# block_diagram.net
KiCad netlist of a schematic drawn in Altium Designer
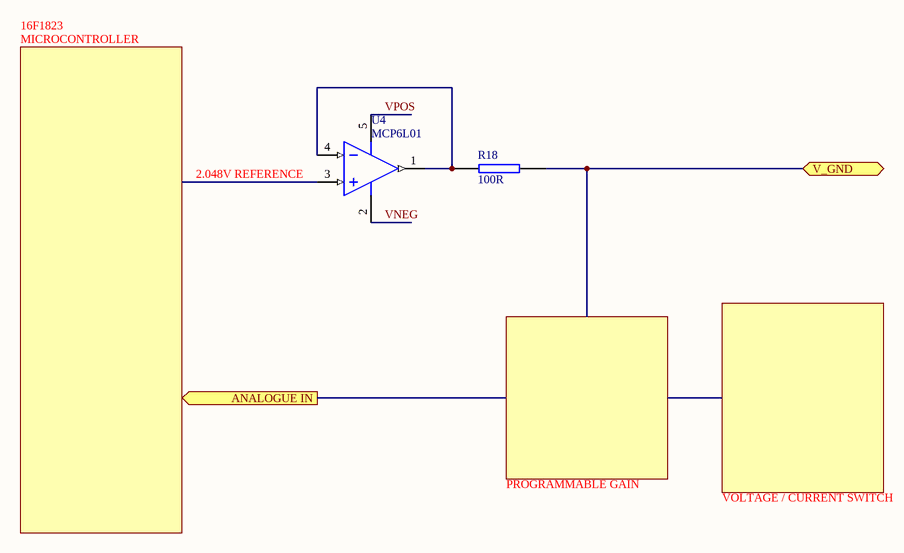
[diagram p0: block diagram.schdoc]

(export (version "E")
  (design (tool "Eeschema 10.0.6"))
  (components
    (comp (ref "R18")
      (value "100R")
      (footprint "RES (3D) - 0603")
      (description "RESISTOR SMD 0603")
      (libsource (lib "NASCO") (part "RES SMD 0603"))
    )
    (comp (ref "U4") (value "MCP6L01") (footprint "SOT23-5AL") (libsource (lib "Schlib1") (part "MCP6L01")))
  )
  (nets
    (net (code "2") (name "/VNEG") (class "Default")
      (node (ref "U4") (pin "2") (pinfunction "GND_2") (pintype "power_in"))
    )
    (net (code "3") (name "/VPOS") (class "Default")
      (node (ref "U4") (pin "5") (pinfunction "V+_5") (pintype "power_in"))
    )
    (net (code "4") (name "/V_GND") (class "Default")
      (node (ref "R18") (pin "2") (pinfunction "2_2") (pintype "passive"))
    )
    (net (code "5") (name "Net-(U4-INA-)") (class "Default")
      (node (ref "R18") (pin "1") (pinfunction "1_1") (pintype "passive"))
      (node (ref "U4") (pin "1") (pinfunction "OUTA_1") (pintype "output"))
      (node (ref "U4") (pin "4") (pinfunction "INA-_4") (pintype "input"))
    )
    (net (code "6") (name "unconnected-(U4-INA+-Pad3)") (class "Default")
      (node (ref "U4") (pin "3") (pinfunction "INA+_3") (pintype "input"))
    )
  )
)
